# 09_-_ETHERNET.net
KiCad netlist of a schematic drawn in Altium Designer
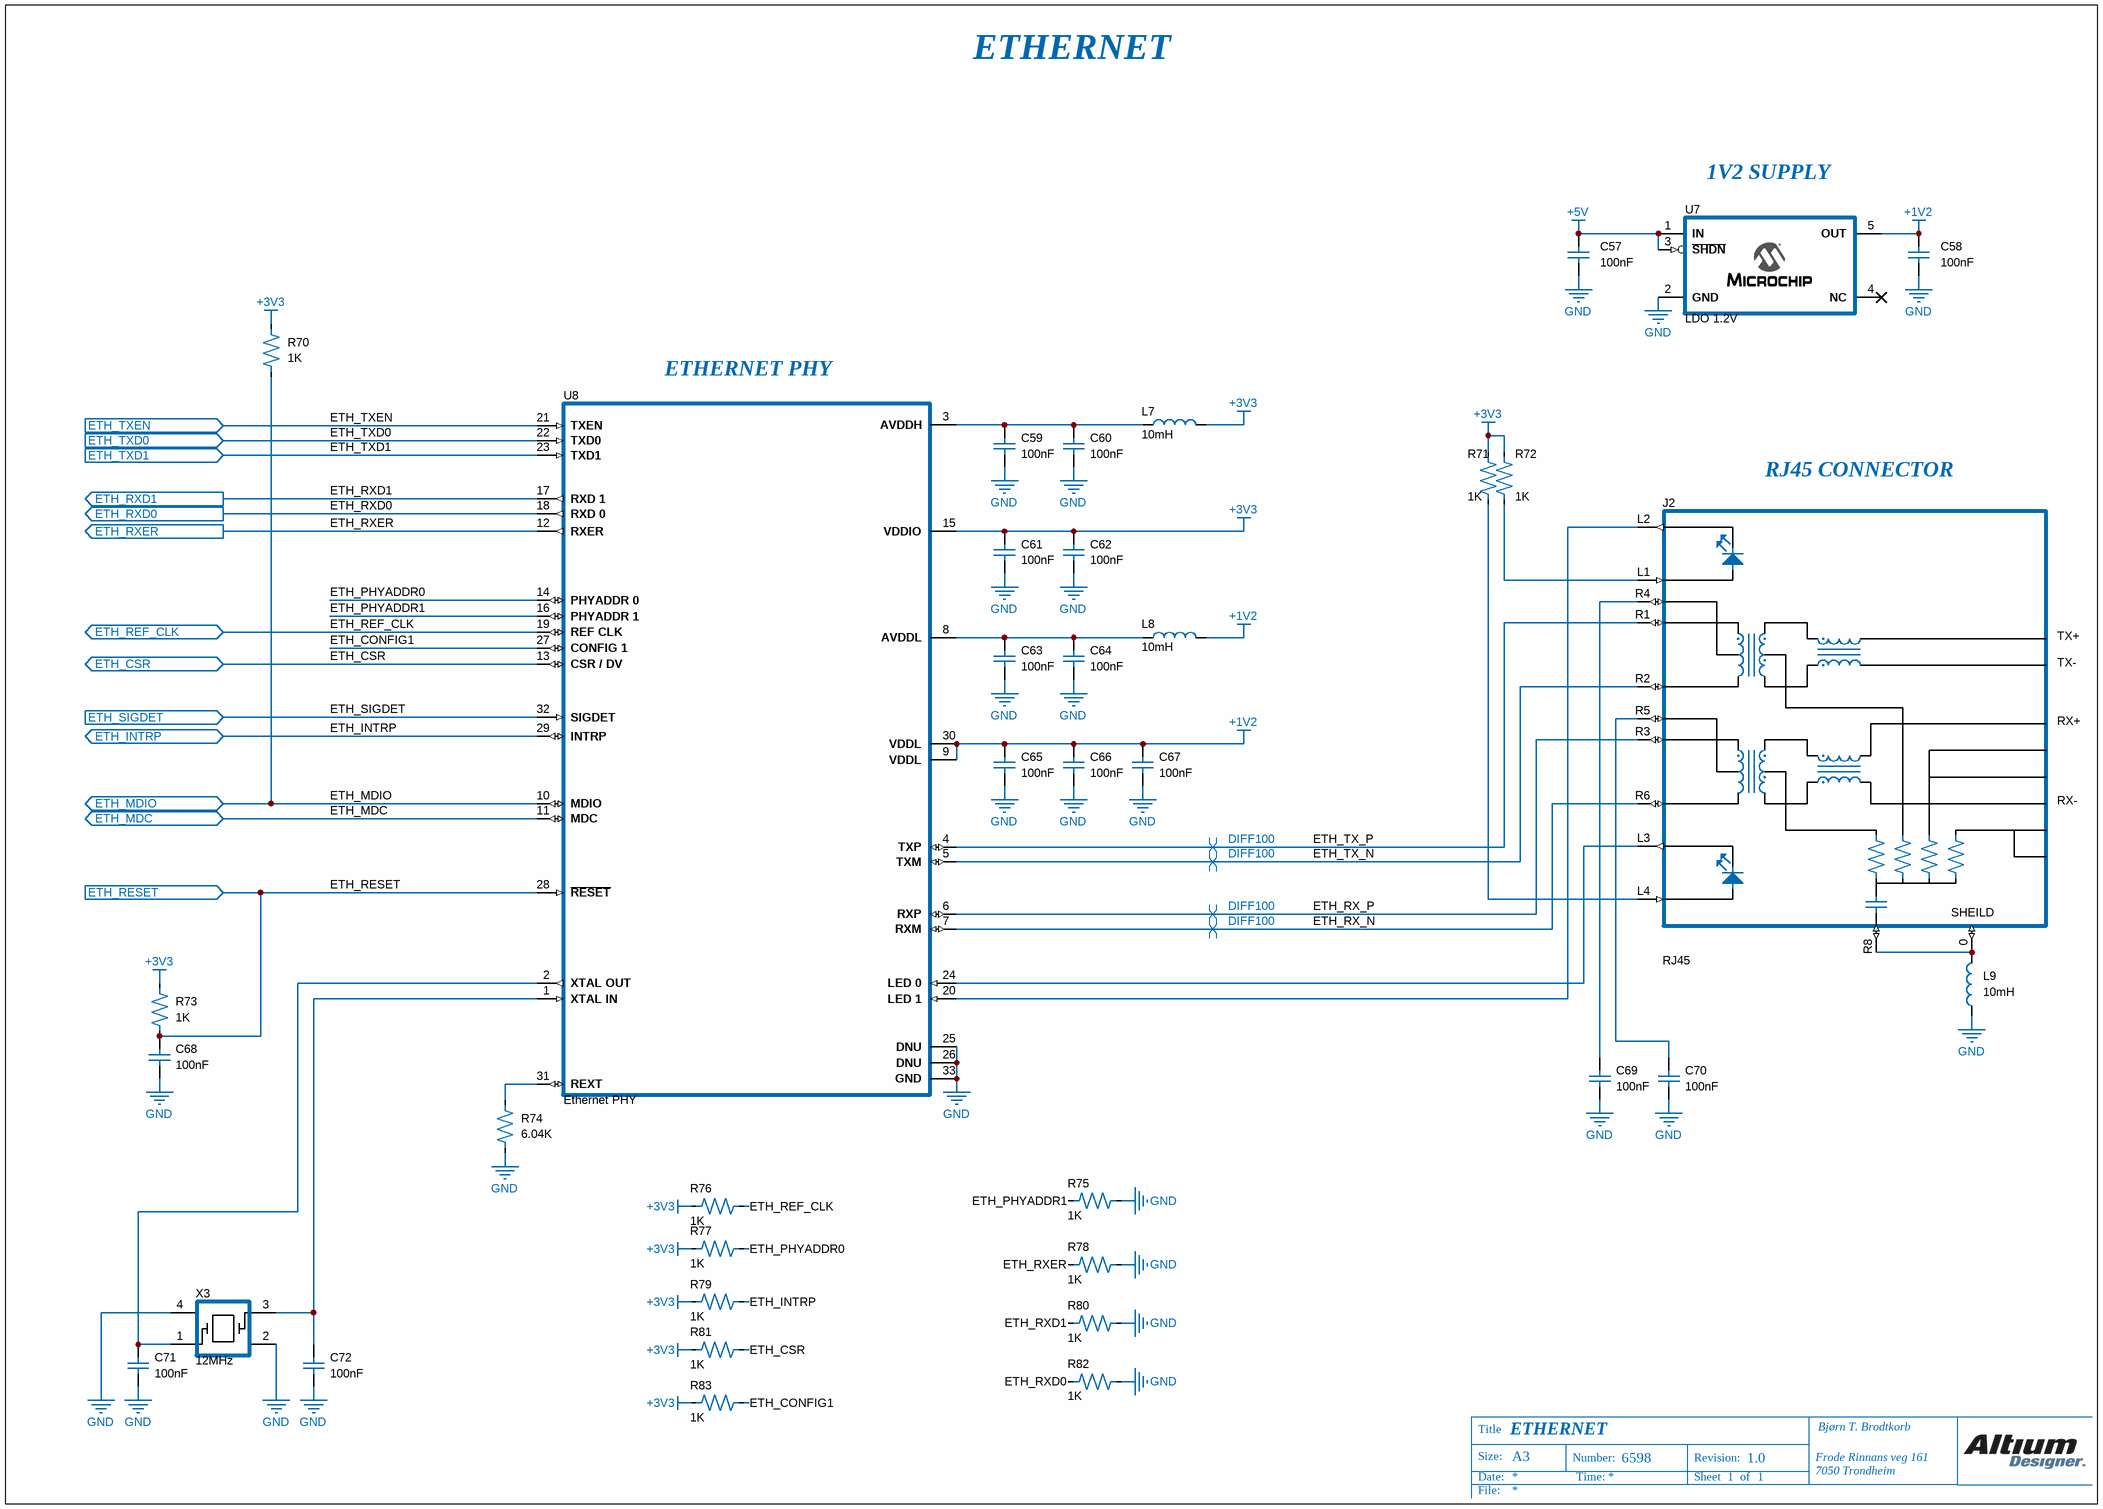
[diagram p0: [09] - ETHERNET.SchDoc]

(export (version "E")
  (design (tool "Eeschema 10.0.6"))
  (components
    (comp (ref "C57")
      (value "100nF")
      (footprint "C0805")
      (description "C0805")
      (fields (field (name "Comment") "08053C105KAT2A"))
      (libsource (lib "Passive components") (part "08053C105KAT2A"))
    )
    (comp (ref "C58")
      (value "100nF")
      (footprint "C0805")
      (description "C0805")
      (fields (field (name "Comment") "08053C105KAT2A"))
      (libsource (lib "Passive components") (part "08053C105KAT2A"))
    )
    (comp (ref "C59")
      (value "100nF")
      (footprint "C0402")
      (description "C0402")
      (fields (field (name "Comment") "04023C103KAT2A"))
      (libsource (lib "Passive components") (part "04023C103KAT2A"))
    )
    (comp (ref "C60")
      (value "100nF")
      (footprint "C0603")
      (description "C0603")
      (fields (field (name "Comment") "02016D104KAT2A"))
      (libsource (lib "Passive components") (part "02016D104KAT2A"))
    )
    (comp (ref "C61")
      (value "100nF")
      (footprint "C0402")
      (description "C0402")
      (fields (field (name "Comment") "04023C103KAT2A"))
      (libsource (lib "Passive components") (part "04023C103KAT2A"))
    )
    (comp (ref "C62")
      (value "100nF")
      (footprint "C0603")
      (description "C0603")
      (fields (field (name "Comment") "02016D104KAT2A"))
      (libsource (lib "Passive components") (part "02016D104KAT2A"))
    )
    (comp (ref "C63")
      (value "100nF")
      (footprint "C0402")
      (description "C0402")
      (fields (field (name "Comment") "04023C103KAT2A"))
      (libsource (lib "Passive components") (part "04023C103KAT2A"))
    )
    (comp (ref "C64")
      (value "100nF")
      (footprint "C0603")
      (description "C0603")
      (fields (field (name "Comment") "02016D104KAT2A"))
      (libsource (lib "Passive components") (part "02016D104KAT2A"))
    )
    (comp (ref "C65")
      (value "100nF")
      (footprint "C0402")
      (description "C0402")
      (fields (field (name "Comment") "04023C103KAT2A"))
      (libsource (lib "Passive components") (part "04023C103KAT2A"))
    )
    (comp (ref "C66")
      (value "100nF")
      (footprint "C0402")
      (description "C0402")
      (fields (field (name "Comment") "04023C103KAT2A"))
      (libsource (lib "Passive components") (part "04023C103KAT2A"))
    )
    (comp (ref "C67")
      (value "100nF")
      (footprint "C0603")
      (description "C0603")
      (fields (field (name "Comment") "02016D104KAT2A"))
      (libsource (lib "Passive components") (part "02016D104KAT2A"))
    )
    (comp (ref "C68")
      (value "100nF")
      (footprint "C0402")
      (description "C0402")
      (fields (field (name "Comment") "04023C103KAT2A"))
      (libsource (lib "Passive components") (part "04023C103KAT2A"))
    )
    (comp (ref "C69")
      (value "100nF")
      (footprint "C0402")
      (description "C0402")
      (fields (field (name "Comment") "04023C103KAT2A"))
      (libsource (lib "Passive components") (part "04023C103KAT2A"))
    )
    (comp (ref "C70")
      (value "100nF")
      (footprint "C0402")
      (description "C0402")
      (fields (field (name "Comment") "04023C103KAT2A"))
      (libsource (lib "Passive components") (part "04023C103KAT2A"))
    )
    (comp (ref "C71")
      (value "100nF")
      (footprint "C0402")
      (description "C0402")
      (fields (field (name "Comment") "04023C103KAT2A"))
      (libsource (lib "Passive components") (part "04023C103KAT2A"))
    )
    (comp (ref "C72")
      (value "100nF")
      (footprint "C0402")
      (description "C0402")
      (fields (field (name "Comment") "04023C103KAT2A"))
      (libsource (lib "Passive components") (part "04023C103KAT2A"))
    )
    (comp (ref "J2")
      (value "RJ45")
      (footprint "RJ45 8P8C LED & magnetics")
      (description "RJ45 8P8C LED & magnetics")
      (libsource (lib "Connectors") (part "234235-2-2-1-12"))
    )
    (comp (ref "L7")
      (value "10mH")
      (footprint "Inductor 0603")
      (description "Inductor 0603")
      (fields (field (name "Comment") "MLZ1608A2R2WT"))
      (libsource (lib "Passive components") (part "MLZ1608A2R2WT"))
    )
    (comp (ref "L8")
      (value "10mH")
      (footprint "Inductor 0603")
      (description "Inductor 0603")
      (fields (field (name "Comment") "MLZ1608A2R2WT"))
      (libsource (lib "Passive components") (part "MLZ1608A2R2WT"))
    )
    (comp (ref "L9")
      (value "10mH")
      (footprint "Inductor 0603")
      (description "Inductor 0603")
      (fields (field (name "Comment") "MLZ1608A2R2WT"))
      (libsource (lib "Passive components") (part "MLZ1608A2R2WT"))
    )
    (comp (ref "R70")
      (value "1K")
      (footprint "R0402")
      (description "R0402")
      (fields (field (name "Comment") "CRCW04020000Z0ED"))
      (libsource (lib "Passive components") (part "CRCW04020000Z0ED"))
    )
    (comp (ref "R71")
      (value "1K")
      (footprint "R0402")
      (description "R0402")
      (fields (field (name "Comment") "CRCW04020000Z0ED"))
      (libsource (lib "Passive components") (part "CRCW04020000Z0ED"))
    )
    (comp (ref "R72")
      (value "1K")
      (footprint "R0402")
      (description "R0402")
      (fields (field (name "Comment") "CRCW04020000Z0ED"))
      (libsource (lib "Passive components") (part "CRCW04020000Z0ED"))
    )
    (comp (ref "R73")
      (value "1K")
      (footprint "R0402")
      (description "R0402")
      (fields (field (name "Comment") "CRCW04020000Z0ED"))
      (libsource (lib "Passive components") (part "CRCW04020000Z0ED"))
    )
    (comp (ref "R74")
      (value "6.04K")
      (footprint "R0402")
      (description "R0402")
      (fields (field (name "Comment") "CRCW04020000Z0ED"))
      (libsource (lib "Passive components") (part "CRCW04020000Z0ED"))
    )
    (comp (ref "R75")
      (value "1K")
      (footprint "R0402")
      (description "R0402")
      (fields (field (name "Comment") "CRCW04020000Z0ED"))
      (libsource (lib "Passive components") (part "CRCW04020000Z0ED"))
    )
    (comp (ref "R76")
      (value "1K")
      (footprint "R0402")
      (description "R0402")
      (fields (field (name "Comment") "CRCW04020000Z0ED"))
      (libsource (lib "Passive components") (part "CRCW04020000Z0ED"))
    )
    (comp (ref "R77")
      (value "1K")
      (footprint "R0402")
      (description "R0402")
      (fields (field (name "Comment") "CRCW04020000Z0ED"))
      (libsource (lib "Passive components") (part "CRCW04020000Z0ED"))
    )
    (comp (ref "R78")
      (value "1K")
      (footprint "R0402")
      (description "R0402")
      (fields (field (name "Comment") "CRCW04020000Z0ED"))
      (libsource (lib "Passive components") (part "CRCW04020000Z0ED"))
    )
    (comp (ref "R79")
      (value "1K")
      (footprint "R0402")
      (description "R0402")
      (fields (field (name "Comment") "CRCW04020000Z0ED"))
      (libsource (lib "Passive components") (part "CRCW04020000Z0ED"))
    )
    (comp (ref "R80")
      (value "1K")
      (footprint "R0402")
      (description "R0402")
      (fields (field (name "Comment") "CRCW04020000Z0ED"))
      (libsource (lib "Passive components") (part "CRCW04020000Z0ED"))
    )
    (comp (ref "R81")
      (value "1K")
      (footprint "R0402")
      (description "R0402")
      (fields (field (name "Comment") "CRCW04020000Z0ED"))
      (libsource (lib "Passive components") (part "CRCW04020000Z0ED"))
    )
    (comp (ref "R82")
      (value "1K")
      (footprint "R0402")
      (description "R0402")
      (fields (field (name "Comment") "CRCW04020000Z0ED"))
      (libsource (lib "Passive components") (part "CRCW04020000Z0ED"))
    )
    (comp (ref "R83")
      (value "1K")
      (footprint "R0402")
      (description "R0402")
      (fields (field (name "Comment") "CRCW04020000Z0ED"))
      (libsource (lib "Passive components") (part "CRCW04020000Z0ED"))
    )
    (comp (ref "U7")
      (value "LDO 1.2V")
      (footprint "MCP1801T-1202I/OT")
      (description "LDO fixed 1.2V 150mA")
      (libsource (lib "Voltage regulators") (part "MCP1801T-1202I/OT"))
    )
    (comp (ref "U8")
      (value "Ethernet PHY")
      (footprint "KSZ8061RNBW")
      (description "Ethernet PHY 10BASE-T / 100BASE-T")
      (libsource (lib "IC") (part "KSZ8061RNBW"))
    )
    (comp (ref "X3")
      (value "12MHz")
      (footprint "MCSJK-7U-12.00-12-30-80-B-30")
      (description "Crystal 12MHz 3.2mm x 2.5mm")
      (libsource (lib "Crystals") (part "MCSJK-7U-12.00-12-30-80-B-30"))
    )
  )
  (nets
    (net (code "1") (name "+1V2") (class "Default")
      (node (ref "C58") (pin "2") (pinfunction "2_2") (pintype "passive"))
      (node (ref "C65") (pin "2") (pinfunction "2_2") (pintype "passive"))
      (node (ref "C66") (pin "2") (pinfunction "2_2") (pintype "passive"))
      (node (ref "C67") (pin "1") (pinfunction "1_1") (pintype "passive"))
      (node (ref "L8") (pin "2") (pinfunction "2_2") (pintype "passive"))
      (node (ref "U7") (pin "5") (pinfunction "OUT_5") (pintype "power_in"))
      (node (ref "U8") (pin "30") (pinfunction "VDDL_30") (pintype "power_in"))
      (node (ref "U8") (pin "9") (pinfunction "VDDL_9") (pintype "power_in"))
    )
    (net (code "2") (name "+3V3") (class "Default")
      (node (ref "C61") (pin "2") (pinfunction "2_2") (pintype "passive"))
      (node (ref "C62") (pin "1") (pinfunction "1_1") (pintype "passive"))
      (node (ref "L7") (pin "2") (pinfunction "2_2") (pintype "passive"))
      (node (ref "R70") (pin "1") (pinfunction "1_1") (pintype "passive"))
      (node (ref "R71") (pin "1") (pinfunction "1_1") (pintype "passive"))
      (node (ref "R72") (pin "1") (pinfunction "1_1") (pintype "passive"))
      (node (ref "R73") (pin "1") (pinfunction "1_1") (pintype "passive"))
      (node (ref "R76") (pin "1") (pinfunction "1_1") (pintype "passive"))
      (node (ref "R77") (pin "1") (pinfunction "1_1") (pintype "passive"))
      (node (ref "R79") (pin "1") (pinfunction "1_1") (pintype "passive"))
      (node (ref "R81") (pin "1") (pinfunction "1_1") (pintype "passive"))
      (node (ref "R83") (pin "1") (pinfunction "1_1") (pintype "passive"))
      (node (ref "U8") (pin "15") (pinfunction "VDDIO_15") (pintype "power_in"))
    )
    (net (code "3") (name "+5V") (class "Default")
      (node (ref "C57") (pin "2") (pinfunction "2_2") (pintype "passive"))
      (node (ref "U7") (pin "1") (pinfunction "IN_1") (pintype "power_in"))
      (node (ref "U7") (pin "3") (pinfunction "~{SHDN}_3") (pintype "input"))
    )
    (net (code "4") (name "/ETH_CONFIG1") (class "Default")
      (node (ref "R83") (pin "2") (pinfunction "3_2") (pintype "passive"))
      (node (ref "U8") (pin "27") (pinfunction "CONFIG_1_27") (pintype "bidirectional"))
    )
    (net (code "5") (name "/ETH_CSR") (class "Default")
      (node (ref "R81") (pin "2") (pinfunction "3_2") (pintype "passive"))
      (node (ref "U8") (pin "13") (pinfunction "CSR_/_DV_13") (pintype "bidirectional"))
    )
    (net (code "6") (name "/ETH_INTRP") (class "Default")
      (node (ref "R79") (pin "2") (pinfunction "3_2") (pintype "passive"))
      (node (ref "U8") (pin "29") (pinfunction "INTRP_29") (pintype "bidirectional"))
    )
    (net (code "7") (name "/ETH_MDC") (class "Default")
      (node (ref "U8") (pin "11") (pinfunction "MDC_11") (pintype "bidirectional"))
    )
    (net (code "8") (name "/ETH_MDIO") (class "Default")
      (node (ref "R70") (pin "2") (pinfunction "3_2") (pintype "passive"))
      (node (ref "U8") (pin "10") (pinfunction "MDIO_10") (pintype "bidirectional"))
    )
    (net (code "9") (name "/ETH_PHYADDR0") (class "Default")
      (node (ref "R77") (pin "2") (pinfunction "3_2") (pintype "passive"))
      (node (ref "U8") (pin "14") (pinfunction "PHYADDR_0_14") (pintype "bidirectional"))
    )
    (net (code "10") (name "/ETH_PHYADDR1") (class "Default")
      (node (ref "R75") (pin "1") (pinfunction "1_1") (pintype "passive"))
      (node (ref "U8") (pin "16") (pinfunction "PHYADDR_1_16") (pintype "bidirectional"))
    )
    (net (code "11") (name "/ETH_REF_CLK") (class "Default")
      (node (ref "R76") (pin "2") (pinfunction "3_2") (pintype "passive"))
      (node (ref "U8") (pin "19") (pinfunction "REF_CLK_19") (pintype "bidirectional"))
    )
    (net (code "12") (name "/ETH_RESET") (class "Default")
      (node (ref "C68") (pin "2") (pinfunction "2_2") (pintype "passive"))
      (node (ref "R73") (pin "2") (pinfunction "3_2") (pintype "passive"))
      (node (ref "U8") (pin "28") (pinfunction "~{RESET}_28") (pintype "input"))
    )
    (net (code "13") (name "/ETH_RXD0") (class "Default")
      (node (ref "R82") (pin "1") (pinfunction "1_1") (pintype "passive"))
      (node (ref "U8") (pin "18") (pinfunction "RXD_0_18") (pintype "output"))
    )
    (net (code "14") (name "/ETH_RXD1") (class "Default")
      (node (ref "R80") (pin "1") (pinfunction "1_1") (pintype "passive"))
      (node (ref "U8") (pin "17") (pinfunction "RXD_1_17") (pintype "output"))
    )
    (net (code "15") (name "/ETH_RXER") (class "Default")
      (node (ref "R78") (pin "1") (pinfunction "1_1") (pintype "passive"))
      (node (ref "U8") (pin "12") (pinfunction "RXER_12") (pintype "output"))
    )
    (net (code "16") (name "/ETH_RX_N") (class "Default")
      (node (ref "J2") (pin "R6") (pintype "bidirectional"))
      (node (ref "U8") (pin "7") (pinfunction "RXM_7") (pintype "bidirectional"))
    )
    (net (code "17") (name "/ETH_RX_P") (class "Default")
      (node (ref "J2") (pin "R3") (pintype "bidirectional"))
      (node (ref "U8") (pin "6") (pinfunction "RXP_6") (pintype "bidirectional"))
    )
    (net (code "18") (name "/ETH_SIGDET") (class "Default")
      (node (ref "U8") (pin "32") (pinfunction "SIGDET_32") (pintype "input"))
    )
    (net (code "19") (name "/ETH_TXD0") (class "Default")
      (node (ref "U8") (pin "22") (pinfunction "TXD0_22") (pintype "input"))
    )
    (net (code "20") (name "/ETH_TXD1") (class "Default")
      (node (ref "U8") (pin "23") (pinfunction "TXD1_23") (pintype "input"))
    )
    (net (code "21") (name "/ETH_TXEN") (class "Default")
      (node (ref "U8") (pin "21") (pinfunction "TXEN_21") (pintype "input"))
    )
    (net (code "22") (name "/ETH_TX_N") (class "Default")
      (node (ref "J2") (pin "R2") (pintype "bidirectional"))
      (node (ref "U8") (pin "5") (pinfunction "TXM_5") (pintype "bidirectional"))
    )
    (net (code "23") (name "/ETH_TX_P") (class "Default")
      (node (ref "J2") (pin "R1") (pintype "bidirectional"))
      (node (ref "U8") (pin "4") (pinfunction "TXP_4") (pintype "bidirectional"))
    )
    (net (code "24") (name "GND") (class "Default")
      (node (ref "C57") (pin "1") (pinfunction "1_1") (pintype "passive"))
      (node (ref "C58") (pin "1") (pinfunction "1_1") (pintype "passive"))
      (node (ref "C59") (pin "1") (pinfunction "1_1") (pintype "passive"))
      (node (ref "C60") (pin "2") (pinfunction "2_2") (pintype "passive"))
      (node (ref "C61") (pin "1") (pinfunction "1_1") (pintype "passive"))
      (node (ref "C62") (pin "2") (pinfunction "2_2") (pintype "passive"))
      (node (ref "C63") (pin "1") (pinfunction "1_1") (pintype "passive"))
      (node (ref "C64") (pin "2") (pinfunction "2_2") (pintype "passive"))
      (node (ref "C65") (pin "1") (pinfunction "1_1") (pintype "passive"))
      (node (ref "C66") (pin "1") (pinfunction "1_1") (pintype "passive"))
      (node (ref "C67") (pin "2") (pinfunction "2_2") (pintype "passive"))
      (node (ref "C68") (pin "1") (pinfunction "1_1") (pintype "passive"))
      (node (ref "C69") (pin "1") (pinfunction "1_1") (pintype "passive"))
      (node (ref "C70") (pin "1") (pinfunction "1_1") (pintype "passive"))
      (node (ref "C71") (pin "1") (pinfunction "1_1") (pintype "passive"))
      (node (ref "C72") (pin "1") (pinfunction "1_1") (pintype "passive"))
      (node (ref "L9") (pin "1") (pinfunction "1_1") (pintype "passive"))
      (node (ref "R74") (pin "2") (pinfunction "3_2") (pintype "passive"))
      (node (ref "R75") (pin "2") (pinfunction "3_2") (pintype "passive"))
      (node (ref "R78") (pin "2") (pinfunction "3_2") (pintype "passive"))
      (node (ref "R80") (pin "2") (pinfunction "3_2") (pintype "passive"))
      (node (ref "R82") (pin "2") (pinfunction "3_2") (pintype "passive"))
      (node (ref "U7") (pin "2") (pinfunction "GND_2") (pintype "power_in"))
      (node (ref "U8") (pin "25") (pinfunction "DNU_25") (pintype "power_in"))
      (node (ref "U8") (pin "26") (pinfunction "DNU_26") (pintype "power_in"))
      (node (ref "U8") (pin "33") (pinfunction "GND_33") (pintype "power_in"))
      (node (ref "X3") (pin "2") (pinfunction "2_2") (pintype "passive"))
      (node (ref "X3") (pin "4") (pinfunction "4_4") (pintype "passive"))
    )
    (net (code "25") (name "Net-(C69-Pad2)") (class "Default")
      (node (ref "C69") (pin "2") (pinfunction "2_2") (pintype "passive"))
      (node (ref "J2") (pin "R4") (pintype "bidirectional"))
    )
    (net (code "26") (name "Net-(C70-Pad2)") (class "Default")
      (node (ref "C70") (pin "2") (pinfunction "2_2") (pintype "passive"))
      (node (ref "J2") (pin "R5") (pintype "bidirectional"))
    )
    (net (code "27") (name "Net-(J2-Pad0)") (class "Default")
      (node (ref "J2") (pin "0") (pintype "bidirectional"))
      (node (ref "J2") (pin "R8") (pintype "bidirectional"))
      (node (ref "L9") (pin "2") (pinfunction "2_2") (pintype "passive"))
    )
    (net (code "28") (name "Net-(R71-3)") (class "Default")
      (node (ref "J2") (pin "L4") (pintype "input"))
      (node (ref "R71") (pin "2") (pinfunction "3_2") (pintype "passive"))
    )
    (net (code "29") (name "Net-(R72-3)") (class "Default")
      (node (ref "J2") (pin "L1") (pintype "input"))
      (node (ref "R72") (pin "2") (pinfunction "3_2") (pintype "passive"))
    )
    (net (code "30") (name "Net-(U8-AVDDH)") (class "Default")
      (node (ref "C59") (pin "2") (pinfunction "2_2") (pintype "passive"))
      (node (ref "C60") (pin "1") (pinfunction "1_1") (pintype "passive"))
      (node (ref "L7") (pin "1") (pinfunction "1_1") (pintype "passive"))
      (node (ref "U8") (pin "3") (pinfunction "AVDDH_3") (pintype "power_in"))
    )
    (net (code "31") (name "Net-(U8-AVDDL)") (class "Default")
      (node (ref "C63") (pin "2") (pinfunction "2_2") (pintype "passive"))
      (node (ref "C64") (pin "1") (pinfunction "1_1") (pintype "passive"))
      (node (ref "L8") (pin "1") (pinfunction "1_1") (pintype "passive"))
      (node (ref "U8") (pin "8") (pinfunction "AVDDL_8") (pintype "power_in"))
    )
    (net (code "32") (name "Net-(U8-LED_0)") (class "Default")
      (node (ref "J2") (pin "L3") (pintype "output"))
      (node (ref "U8") (pin "24") (pinfunction "LED_0_24") (pintype "input"))
    )
    (net (code "33") (name "Net-(U8-LED_1)") (class "Default")
      (node (ref "J2") (pin "L2") (pintype "output"))
      (node (ref "U8") (pin "20") (pinfunction "LED_1_20") (pintype "input"))
    )
    (net (code "34") (name "Net-(U8-REXT)") (class "Default")
      (node (ref "R74") (pin "1") (pinfunction "1_1") (pintype "passive"))
      (node (ref "U8") (pin "31") (pinfunction "REXT_31") (pintype "bidirectional"))
    )
    (net (code "35") (name "Net-(U8-XTAL_IN)") (class "Default")
      (node (ref "C72") (pin "2") (pinfunction "2_2") (pintype "passive"))
      (node (ref "U8") (pin "1") (pinfunction "XTAL_IN_1") (pintype "input"))
      (node (ref "X3") (pin "3") (pinfunction "2_3") (pintype "passive"))
    )
    (net (code "36") (name "Net-(U8-XTAL_OUT)") (class "Default")
      (node (ref "C71") (pin "2") (pinfunction "2_2") (pintype "passive"))
      (node (ref "U8") (pin "2") (pinfunction "XTAL_OUT_2") (pintype "output"))
      (node (ref "X3") (pin "1") (pinfunction "2_1") (pintype "passive"))
    )
    (net (code "37") (name "unconnected-(J2-Pad1)") (class "Default")
      (node (ref "J2") (pin "1") (pinfunction "1_1") (pintype "passive"))
    )
    (net (code "38") (name "unconnected-(J2-Pad1)_1") (class "Default")
      (node (ref "J2") (pin "1") (pinfunction "1_1") (pintype "passive"))
    )
    (net (code "39") (name "unconnected-(J2-Pad2)") (class "Default")
      (node (ref "J2") (pin "2") (pinfunction "2_2") (pintype "passive"))
    )
    (net (code "40") (name "unconnected-(J2-Pad2)_1") (class "Default")
      (node (ref "J2") (pin "2") (pinfunction "2_2") (pintype "passive"))
    )
    (net (code "41") (name "unconnected-(U7-NC-Pad4)") (class "Default")
      (node (ref "U7") (pin "4") (pinfunction "NC_4") (pintype "passive+no_connect"))
    )
  )
)
